# HRT_23D_EBS1_1.net
KiCad netlist of a schematic drawn in Altium Designer
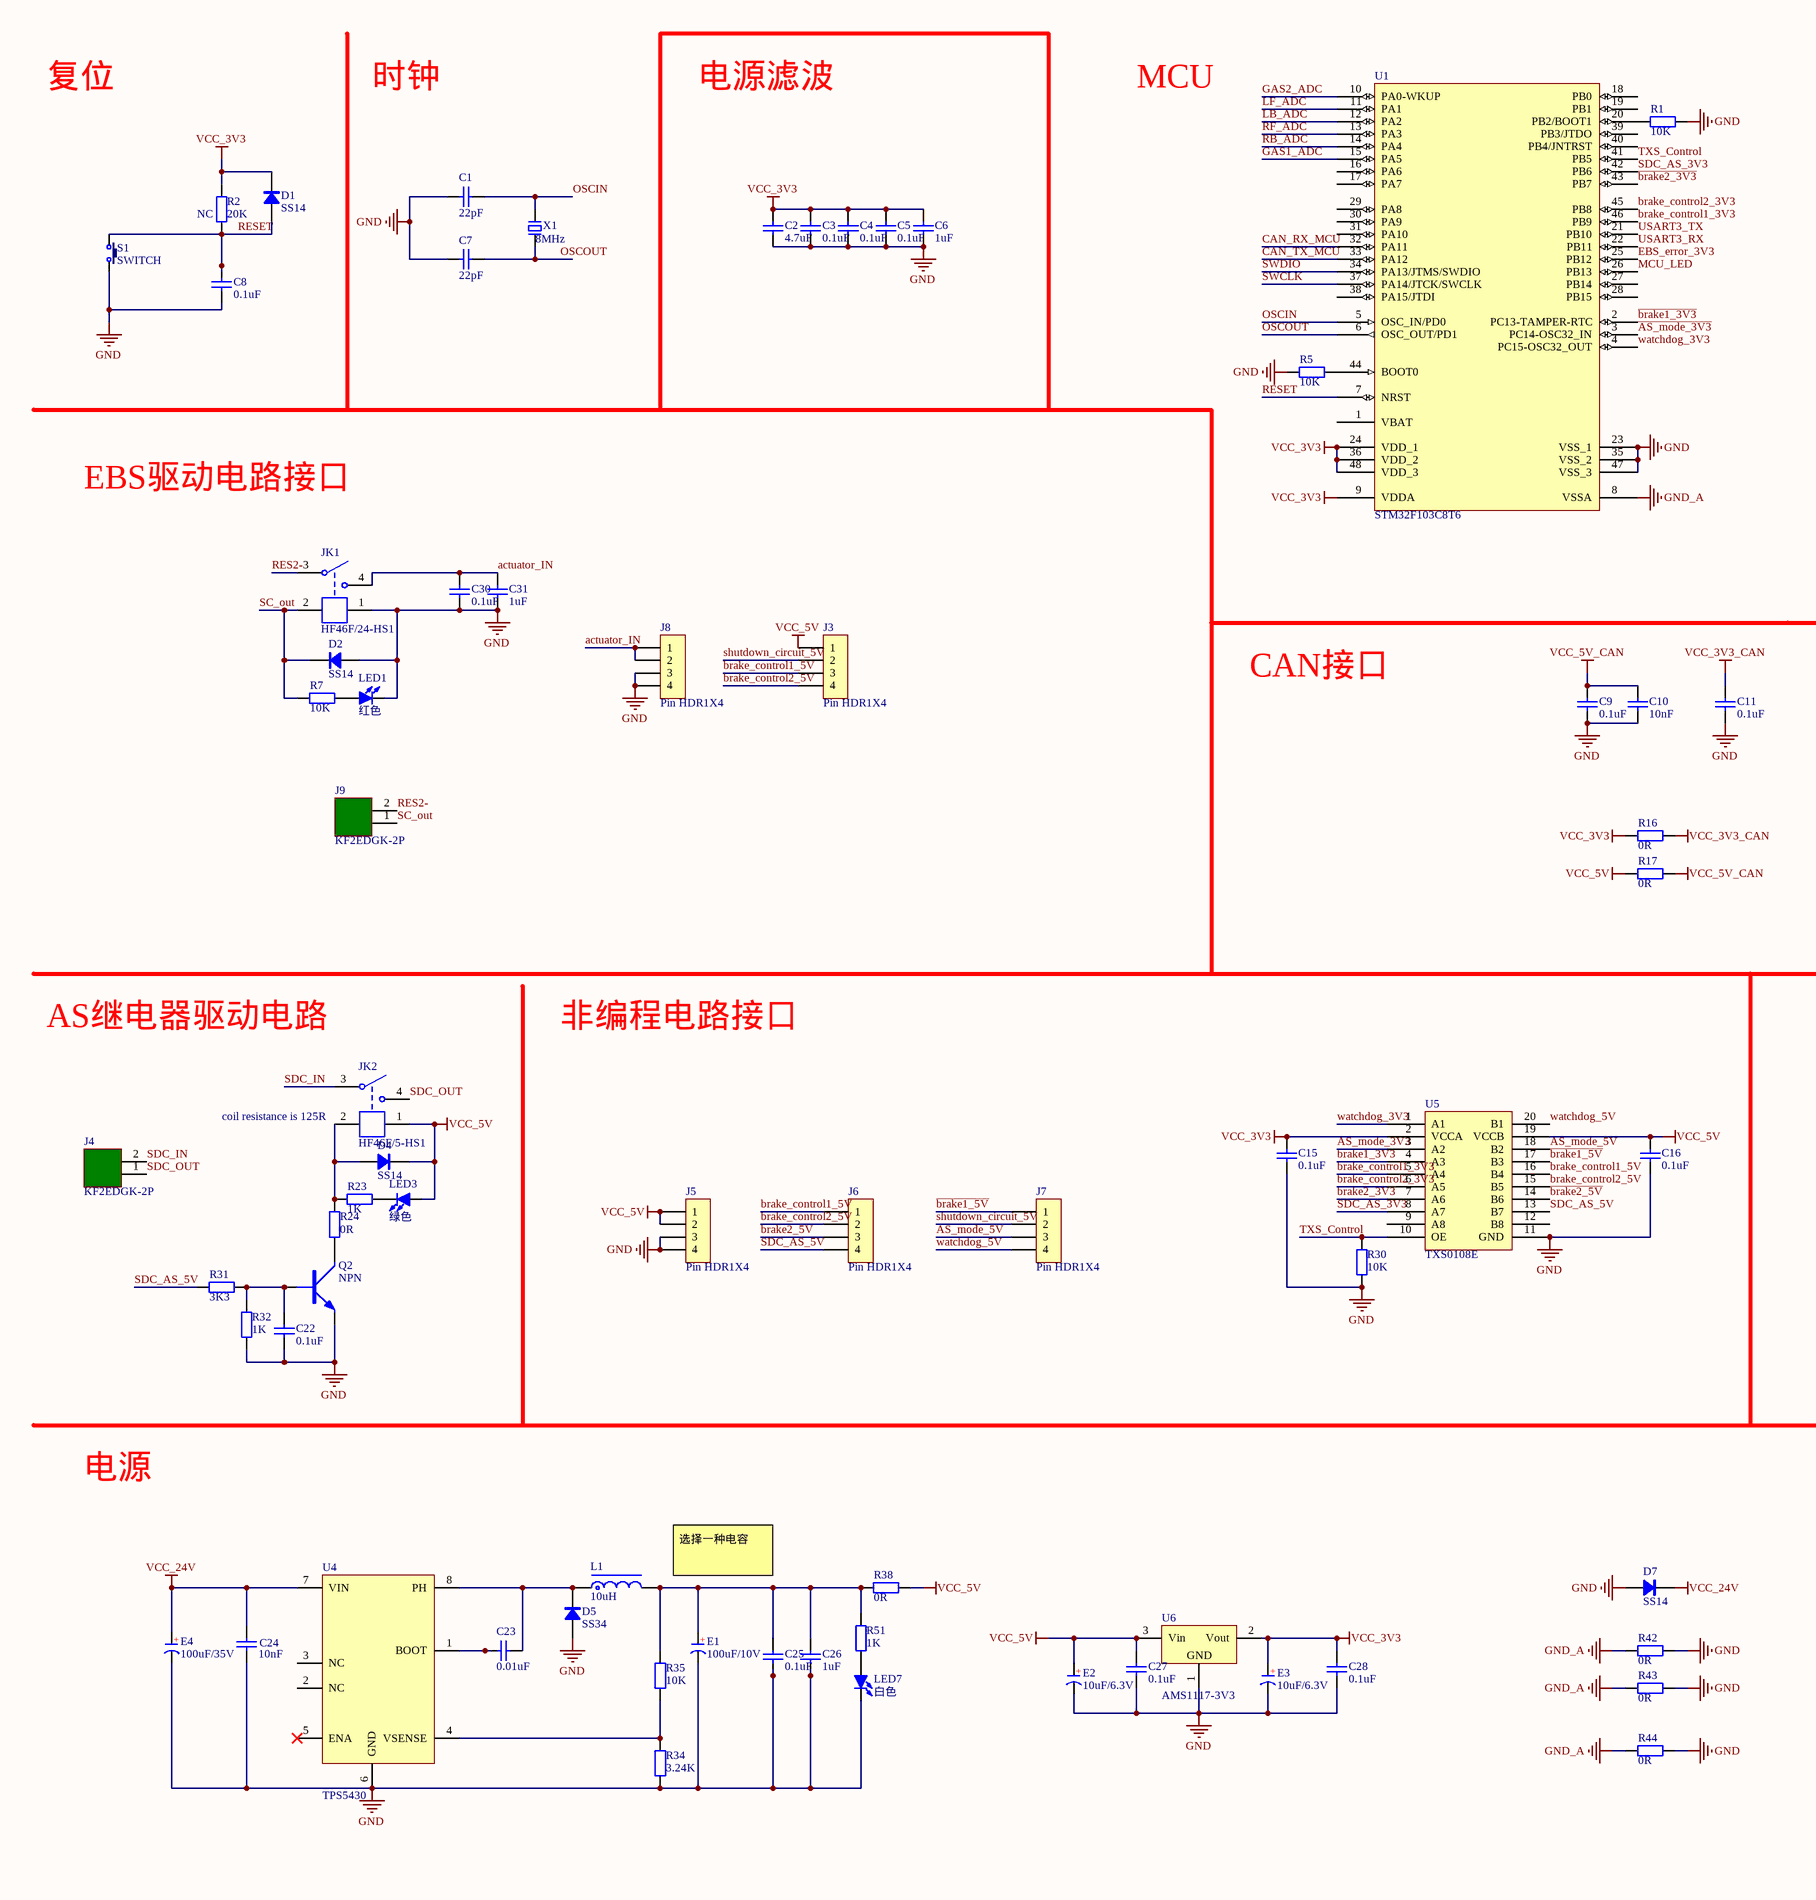
[diagram p0: HRT_23D_EBS1.1.SchDoc, left]
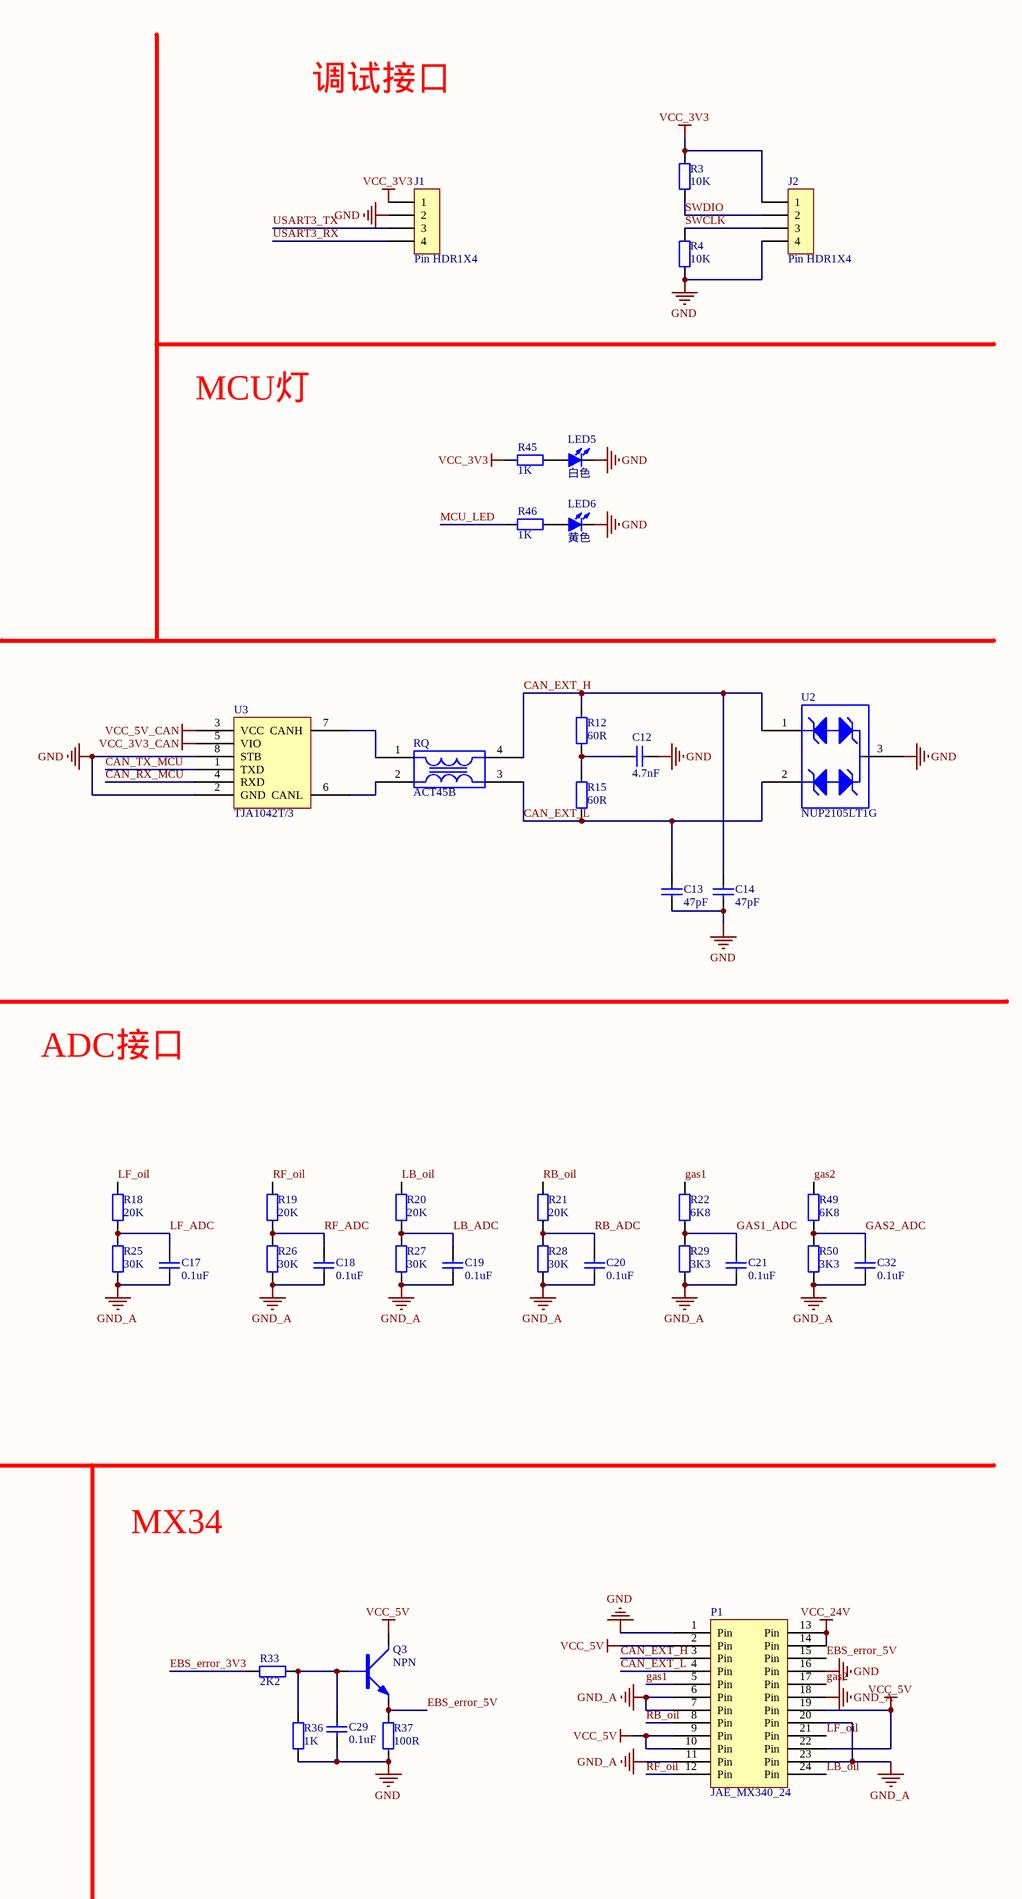
[diagram p1: HRT_23D_EBS1.1.SchDoc, right]

(export (version "E")
  (design (tool "Eeschema 10.0.6"))
  (components
    (comp (ref "C1")
      (value "22pF")
      (footprint "C 0805_M")
      (description "无极性贴片电容")
      (libsource (lib "mainlib") (part "C"))
    )
    (comp (ref "C2")
      (value "4.7uF")
      (footprint "C 0805_M")
      (description "无极性贴片电容")
      (libsource (lib "mainlib") (part "C"))
    )
    (comp (ref "C3")
      (value "0.1uF")
      (footprint "C 0805_M")
      (description "无极性贴片电容")
      (libsource (lib "mainlib") (part "C"))
    )
    (comp (ref "C4")
      (value "0.1uF")
      (footprint "C 0805_M")
      (description "无极性贴片电容")
      (libsource (lib "mainlib") (part "C"))
    )
    (comp (ref "C5")
      (value "0.1uF")
      (footprint "C 0805_M")
      (description "无极性贴片电容")
      (libsource (lib "mainlib") (part "C"))
    )
    (comp (ref "C6")
      (value "1uF")
      (footprint "C 0805_M")
      (description "无极性贴片电容")
      (libsource (lib "mainlib") (part "C"))
    )
    (comp (ref "C7")
      (value "22pF")
      (footprint "C 0805_M")
      (description "无极性贴片电容")
      (libsource (lib "mainlib") (part "C"))
    )
    (comp (ref "C8")
      (value "0.1uF")
      (footprint "C 0805_M")
      (description "无极性贴片电容")
      (libsource (lib "mainlib") (part "C"))
    )
    (comp (ref "C9")
      (value "0.1uF")
      (footprint "C 0805_M")
      (description "无极性贴片电容")
      (libsource (lib "mainlib") (part "C"))
    )
    (comp (ref "C10")
      (value "10nF")
      (footprint "C 0805_M")
      (description "无极性贴片电容")
      (libsource (lib "mainlib") (part "C"))
    )
    (comp (ref "C11")
      (value "0.1uF")
      (footprint "C 0805_M")
      (description "无极性贴片电容")
      (libsource (lib "mainlib") (part "C"))
    )
    (comp (ref "C12")
      (value "4.7nF")
      (footprint "C 0805_M")
      (description "无极性贴片电容")
      (libsource (lib "mainlib") (part "C"))
    )
    (comp (ref "C13")
      (value "47pF")
      (footprint "C 0805_M")
      (description "无极性贴片电容")
      (libsource (lib "mainlib") (part "C"))
    )
    (comp (ref "C14")
      (value "47pF")
      (footprint "C 0805_M")
      (description "无极性贴片电容")
      (libsource (lib "mainlib") (part "C"))
    )
    (comp (ref "C15")
      (value "0.1uF")
      (footprint "C 0805_M")
      (description "无极性贴片电容")
      (libsource (lib "mainlib") (part "C"))
    )
    (comp (ref "C16")
      (value "0.1uF")
      (footprint "C 0805_M")
      (description "无极性贴片电容")
      (libsource (lib "mainlib") (part "C"))
    )
    (comp (ref "C17")
      (value "0.1uF")
      (footprint "C 0805_M")
      (description "无极性贴片电容")
      (libsource (lib "mainlib") (part "C"))
    )
    (comp (ref "C18")
      (value "0.1uF")
      (footprint "C 0805_M")
      (description "无极性贴片电容")
      (libsource (lib "mainlib") (part "C"))
    )
    (comp (ref "C19")
      (value "0.1uF")
      (footprint "C 0805_M")
      (description "无极性贴片电容")
      (libsource (lib "mainlib") (part "C"))
    )
    (comp (ref "C20")
      (value "0.1uF")
      (footprint "C 0805_M")
      (description "无极性贴片电容")
      (libsource (lib "mainlib") (part "C"))
    )
    (comp (ref "C21")
      (value "0.1uF")
      (footprint "C 0805_M")
      (description "无极性贴片电容")
      (libsource (lib "mainlib") (part "C"))
    )
    (comp (ref "C22")
      (value "0.1uF")
      (footprint "C 0805_M")
      (description "无极性贴片电容")
      (libsource (lib "mainlib") (part "C"))
    )
    (comp (ref "C23")
      (value "0.01uF")
      (footprint "C 0805_M")
      (description "无极性贴片电容")
      (libsource (lib "mainlib") (part "C"))
    )
    (comp (ref "C24")
      (value "10nF")
      (footprint "C 0805_M")
      (description "无极性贴片电容")
      (libsource (lib "mainlib") (part "C"))
    )
    (comp (ref "C25")
      (value "0.1uF")
      (footprint "C 0805_M")
      (description "无极性贴片电容")
      (libsource (lib "mainlib") (part "C"))
    )
    (comp (ref "C26")
      (value "1uF")
      (footprint "C 0805_M")
      (description "无极性贴片电容")
      (libsource (lib "mainlib") (part "C"))
    )
    (comp (ref "C27")
      (value "0.1uF")
      (footprint "C 0805_M")
      (description "无极性贴片电容")
      (libsource (lib "mainlib") (part "C"))
    )
    (comp (ref "C28")
      (value "0.1uF")
      (footprint "C 0805_M")
      (description "无极性贴片电容")
      (libsource (lib "mainlib") (part "C"))
    )
    (comp (ref "C29")
      (value "0.1uF")
      (footprint "C 0805_M")
      (description "无极性贴片电容")
      (libsource (lib "mainlib") (part "C"))
    )
    (comp (ref "C30")
      (value "0.1uF")
      (footprint "C 0805_M")
      (description "无极性贴片电容")
      (libsource (lib "mainlib") (part "C"))
    )
    (comp (ref "C31")
      (value "1uF")
      (footprint "C 0805_M")
      (description "无极性贴片电容")
      (libsource (lib "mainlib") (part "C"))
    )
    (comp (ref "C32")
      (value "0.1uF")
      (footprint "C 0805_M")
      (description "无极性贴片电容")
      (libsource (lib "mainlib") (part "C"))
    )
    (comp (ref "D1")
      (value "SS14")
      (footprint "SMA")
      (description "肖特基二极管")
      (fields (field (name "版权归属") "源创客"))
      (libsource (lib "mainlib") (part "SS14"))
    )
    (comp (ref "D2")
      (value "SS14")
      (footprint "SMA")
      (description "肖特基二极管")
      (fields (field (name "版权归属") "源创客"))
      (libsource (lib "mainlib") (part "SS14"))
    )
    (comp (ref "D4")
      (value "SS14")
      (footprint "SMA")
      (description "肖特基二极管")
      (fields (field (name "版权归属") "源创客"))
      (libsource (lib "mainlib") (part "SS14"))
    )
    (comp (ref "D5")
      (value "SS34")
      (footprint "SMA")
      (description "肖特基二极管")
      (fields (field (name "版权归属") "源创客"))
      (libsource (lib "mainlib") (part "SS34"))
    )
    (comp (ref "D7")
      (value "SS14")
      (footprint "SMA")
      (description "肖特基二极管")
      (fields (field (name "版权归属") "源创客"))
      (libsource (lib "mainlib") (part "SS14"))
    )
    (comp (ref "E1")
      (value "100uF/10V")
      (footprint "CM C(5*5.4)")
      (description "贴片电解电容\r\nESR < 0.04R")
      (fields (field (name "版权归属") "源创客"))
      (libsource (lib "mainlib") (part "C-CM"))
    )
    (comp (ref "E2")
      (value "10uF/6.3V")
      (footprint "CD A(3216)")
      (description "贴片钽电容")
      (fields (field (name "版权归属") "源创客"))
      (libsource (lib "mainlib") (part "C-CD"))
    )
    (comp (ref "E3")
      (value "10uF/6.3V")
      (footprint "CD A(3216)")
      (description "贴片钽电容")
      (fields (field (name "版权归属") "源创客"))
      (libsource (lib "mainlib") (part "C-CD"))
    )
    (comp (ref "E4")
      (value "100uF/35V")
      (footprint "CM D(6.3*7.7)")
      (description "贴片电解电容\r\nESR < 0.04R")
      (fields (field (name "版权归属") "源创客"))
      (libsource (lib "mainlib") (part "C-CM"))
    )
    (comp (ref "J1")
      (value "Pin HDR1X4")
      (footprint "Pin HDR1X4/2.54mm-S")
      (libsource (lib "mainlib") (part "Pin HDR1X4"))
    )
    (comp (ref "J2")
      (value "Pin HDR1X4")
      (footprint "Pin HDR1X4/2.54mm-S")
      (libsource (lib "mainlib") (part "Pin HDR1X4"))
    )
    (comp (ref "J3")
      (value "Pin HDR1X4")
      (footprint "Fe-HDR1X4/2.54-S")
      (libsource (lib "mainlib") (part "Pin HDR1X4"))
    )
    (comp (ref "J4")
      (value "KF2EDGK-2P")
      (footprint "KF2EDGK5.08W-2P")
      (libsource (lib "mainlib") (part "KF2EDGK-2P"))
    )
    (comp (ref "J5")
      (value "Pin HDR1X4")
      (footprint "Fe-HDR1X4/2.54-S")
      (libsource (lib "mainlib") (part "Pin HDR1X4"))
    )
    (comp (ref "J6")
      (value "Pin HDR1X4")
      (footprint "Fe-HDR1X4/2.54-S")
      (libsource (lib "mainlib") (part "Pin HDR1X4"))
    )
    (comp (ref "J7")
      (value "Pin HDR1X4")
      (footprint "Fe-HDR1X4/2.54-S")
      (libsource (lib "mainlib") (part "Pin HDR1X4"))
    )
    (comp (ref "J8")
      (value "Pin HDR1X4")
      (footprint "Fe-HDR1X4/2.54-S")
      (libsource (lib "mainlib") (part "Pin HDR1X4"))
    )
    (comp (ref "J9")
      (value "KF2EDGK-2P")
      (footprint "KF2EDGK5.08W-2P")
      (libsource (lib "mainlib") (part "KF2EDGK-2P"))
    )
    (comp (ref "JK1")
      (value "HF46F/24-HS1")
      (footprint "HF46-xx-HS1")
      (description "24V一组常开继电器")
      (fields (field (name "版权归属") "源创客"))
      (libsource (lib "mainlib") (part "HF46F/24-HS1"))
    )
    (comp (ref "JK2")
      (value "HF46F/5-HS1")
      (footprint "HF46-xx-HS1")
      (description "5V一组常开")
      (fields (field (name "版权归属") "源创客"))
      (libsource (lib "mainlib") (part "HF46F/5-HS1"))
    )
    (comp (ref "L1")
      (value "10uH")
      (footprint "SMD 12*12*8mm")
      (description "贴片功率电感")
      (fields (field (name "版权归属") "源创客"))
      (libsource (lib "mainlib") (part "L-CD"))
    )
    (comp (ref "LED1")
      (value "红色")
      (footprint "LED 0805R")
      (description "贴片LED")
      (fields (field (name "版权归属") "源创客"))
      (libsource (lib "mainlib") (part "LED-SMD"))
    )
    (comp (ref "LED3")
      (value "绿色")
      (footprint "LED 0805G")
      (description "贴片LED")
      (fields (field (name "版权归属") "源创客"))
      (libsource (lib "mainlib") (part "LED-SMD"))
    )
    (comp (ref "LED5")
      (value "白色")
      (footprint "LED 0805W")
      (description "贴片LED")
      (fields (field (name "版权归属") "源创客"))
      (libsource (lib "mainlib") (part "LED-SMD"))
    )
    (comp (ref "LED6")
      (value "黄色")
      (footprint "LED 0805Y")
      (description "贴片LED")
      (fields (field (name "版权归属") "源创客"))
      (libsource (lib "mainlib") (part "LED-SMD"))
    )
    (comp (ref "LED7")
      (value "白色")
      (footprint "LED 0805W")
      (description "贴片LED")
      (fields (field (name "版权归属") "源创客"))
      (libsource (lib "mainlib") (part "LED-SMD"))
    )
    (comp (ref "P1")
      (value "JAE_MX340_24")
      (footprint "JAE_MX34_2.2_24 - duplicate")
      (libsource (lib "mainlib") (part "JAE_MX34024NF1"))
    )
    (comp (ref "Q2")
      (value "NPN")
      (footprint "SOT-23")
      (description "NPN三极管")
      (libsource (lib "mainlib") (part "NPN"))
    )
    (comp (ref "Q3")
      (value "NPN")
      (footprint "SOT-23")
      (description "NPN三极管")
      (libsource (lib "mainlib") (part "NPN"))
    )
    (comp (ref "R1")
      (value "10K")
      (footprint "0805R")
      (description "贴片电阻")
      (libsource (lib "") (part "RES_1"))
    )
    (comp (ref "R2")
      (value "20K")
      (footprint "0805R")
      (description "贴片电阻")
      (libsource (lib "mainlib") (part "RES"))
    )
    (comp (ref "R3")
      (value "10K")
      (footprint "0805R")
      (description "贴片电阻")
      (libsource (lib "mainlib") (part "RES"))
    )
    (comp (ref "R4")
      (value "10K")
      (footprint "0805R")
      (description "贴片电阻")
      (libsource (lib "mainlib") (part "RES"))
    )
    (comp (ref "R5")
      (value "10K")
      (footprint "0805R")
      (description "贴片电阻")
      (libsource (lib "") (part "RES_2"))
    )
    (comp (ref "R7")
      (value "10K")
      (footprint "0805R")
      (description "贴片电阻")
      (libsource (lib "") (part "RES_1"))
    )
    (comp (ref "R12")
      (value "60R")
      (footprint "0805R")
      (description "贴片电阻")
      (libsource (lib "mainlib") (part "RES"))
    )
    (comp (ref "R15")
      (value "60R")
      (footprint "0805R")
      (description "贴片电阻")
      (libsource (lib "mainlib") (part "RES"))
    )
    (comp (ref "R16")
      (value "0R")
      (footprint "0805R")
      (description "贴片电阻")
      (libsource (lib "") (part "RES_2"))
    )
    (comp (ref "R17")
      (value "0R")
      (footprint "0805R")
      (description "贴片电阻")
      (libsource (lib "") (part "RES_2"))
    )
    (comp (ref "R18")
      (value "20K")
      (footprint "0805R")
      (description "贴片电阻")
      (libsource (lib "mainlib") (part "RES"))
    )
    (comp (ref "R19")
      (value "20K")
      (footprint "0805R")
      (description "贴片电阻")
      (libsource (lib "mainlib") (part "RES"))
    )
    (comp (ref "R20")
      (value "20K")
      (footprint "0805R")
      (description "贴片电阻")
      (libsource (lib "mainlib") (part "RES"))
    )
    (comp (ref "R21")
      (value "20K")
      (footprint "0805R")
      (description "贴片电阻")
      (libsource (lib "mainlib") (part "RES"))
    )
    (comp (ref "R22")
      (value "6K8")
      (footprint "0805R")
      (description "贴片电阻")
      (libsource (lib "mainlib") (part "RES"))
    )
    (comp (ref "R23")
      (value "1K")
      (footprint "0805R")
      (description "贴片电阻")
      (libsource (lib "") (part "RES_1"))
    )
    (comp (ref "R24")
      (value "0R")
      (footprint "0805R")
      (description "贴片电阻")
      (libsource (lib "") (part "RES_3"))
    )
    (comp (ref "R25")
      (value "30K")
      (footprint "0805R")
      (description "贴片电阻")
      (libsource (lib "mainlib") (part "RES"))
    )
    (comp (ref "R26")
      (value "30K")
      (footprint "0805R")
      (description "贴片电阻")
      (libsource (lib "mainlib") (part "RES"))
    )
    (comp (ref "R27")
      (value "30K")
      (footprint "0805R")
      (description "贴片电阻")
      (libsource (lib "mainlib") (part "RES"))
    )
    (comp (ref "R28")
      (value "30K")
      (footprint "0805R")
      (description "贴片电阻")
      (libsource (lib "mainlib") (part "RES"))
    )
    (comp (ref "R29")
      (value "3K3")
      (footprint "0805R")
      (description "贴片电阻")
      (libsource (lib "mainlib") (part "RES"))
    )
    (comp (ref "R30")
      (value "10K")
      (footprint "0805R")
      (description "贴片电阻")
      (libsource (lib "mainlib") (part "RES"))
    )
    (comp (ref "R31")
      (value "3K3")
      (footprint "0805R")
      (description "贴片电阻")
      (libsource (lib "") (part "RES_1"))
    )
    (comp (ref "R32")
      (value "1K")
      (footprint "0805R")
      (description "贴片电阻")
      (libsource (lib "mainlib") (part "RES"))
    )
    (comp (ref "R33")
      (value "2K2")
      (footprint "0805R")
      (description "贴片电阻")
      (libsource (lib "") (part "RES_1"))
    )
    (comp (ref "R34")
      (value "3.24K")
      (footprint "0805R")
      (description "贴片电阻")
      (libsource (lib "mainlib") (part "RES"))
    )
    (comp (ref "R35")
      (value "10K")
      (footprint "0805R")
      (description "贴片电阻")
      (libsource (lib "mainlib") (part "RES"))
    )
    (comp (ref "R36")
      (value "1K")
      (footprint "0805R")
      (description "贴片电阻")
      (libsource (lib "mainlib") (part "RES"))
    )
    (comp (ref "R37")
      (value "100R")
      (footprint "0805R")
      (description "贴片电阻")
      (libsource (lib "mainlib") (part "RES"))
    )
    (comp (ref "R38")
      (value "0R")
      (footprint "1206R")
      (description "贴片电阻")
      (libsource (lib "") (part "RES_1"))
    )
    (comp (ref "R42")
      (value "0R")
      (footprint "0805R")
      (description "贴片电阻")
      (libsource (lib "") (part "RES_1"))
    )
    (comp (ref "R43")
      (value "0R")
      (footprint "0805R")
      (description "贴片电阻")
      (libsource (lib "") (part "RES_1"))
    )
    (comp (ref "R44")
      (value "0R")
      (footprint "0805R")
      (description "贴片电阻")
      (libsource (lib "") (part "RES_1"))
    )
    (comp (ref "R45")
      (value "1K")
      (footprint "0805R")
      (description "贴片电阻")
      (libsource (lib "") (part "RES_1"))
    )
    (comp (ref "R46")
      (value "1K")
      (footprint "0805R")
      (description "贴片电阻")
      (libsource (lib "") (part "RES_1"))
    )
    (comp (ref "R49")
      (value "6K8")
      (footprint "0805R")
      (description "贴片电阻")
      (libsource (lib "mainlib") (part "RES"))
    )
    (comp (ref "R50")
      (value "3K3")
      (footprint "0805R")
      (description "贴片电阻")
      (libsource (lib "mainlib") (part "RES"))
    )
    (comp (ref "R51")
      (value "1K")
      (footprint "0805R")
      (description "贴片电阻")
      (libsource (lib "mainlib") (part "RES"))
    )
    (comp (ref "RQ")
      (value "ACT45B")
      (footprint "4532")
      (description "共模电感")
      (libsource (lib "mainlib") (part "ACT45B"))
    )
    (comp (ref "S1")
      (value "SWITCH")
      (footprint "TSW SMD-3*6*2.5")
      (description "按键")
      (libsource (lib "mainlib") (part "SWITCH"))
    )
    (comp (ref "U1")
      (value "STM32F103C8T6")
      (footprint "LQFP48 7X7")
      (libsource (lib "mainlib") (part "STM32F103C8T6"))
    )
    (comp (ref "U2")
      (value "NUP2105LT1G")
      (footprint "SOT-23-3P")
      (description "静电管")
      (libsource (lib "mainlib") (part "NUP2105LT1G"))
    )
    (comp (ref "U3")
      (value "TJA1042T/3")
      (footprint "SOP8")
      (description "高速CAN收发器")
      (libsource (lib "HRT_19D_EBS1.1") (part "TJA1042T/3"))
    )
    (comp (ref "U4")
      (value "TPS5430")
      (footprint "SOP8-Pad")
      (description "DCDC降压芯片")
      (libsource (lib "mainlib") (part "TPS5430"))
    )
    (comp (ref "U5")
      (value "TXS0108E")
      (footprint "SSOP20")
      (libsource (lib "digital_chips") (part "TXS0108E"))
    )
    (comp (ref "U6")
      (value "AMS1117-3V3")
      (footprint "SOT223_M")
      (description "三端稳压芯片")
      (fields (field (name "版权归属") "源创客"))
      (libsource (lib "mainlib") (part "AMS1117"))
    )
    (comp (ref "X1")
      (value "8MHz")
      (footprint "OSC 5032-2P")
      (description "两脚无源晶振")
      (libsource (lib "mainlib") (part "XTAL-2P"))
    )
  )
  (nets
    (net (code "1") (name "/CAN_EXT_H") (class "Default")
      (node (ref "C14") (pin "1") (pinfunction "1_1") (pintype "passive"))
      (node (ref "P1") (pin "3") (pinfunction "Pin_3") (pintype "passive"))
      (node (ref "R12") (pin "2") (pinfunction "2_2") (pintype "passive"))
      (node (ref "RQ") (pin "4") (pinfunction "4_4") (pintype "passive"))
      (node (ref "U2") (pin "1") (pinfunction "1_1") (pintype "passive"))
    )
    (net (code "2") (name "/CAN_EXT_L") (class "Default")
      (node (ref "C13") (pin "1") (pinfunction "1_1") (pintype "passive"))
      (node (ref "P1") (pin "4") (pinfunction "Pin_4") (pintype "passive"))
      (node (ref "R15") (pin "1") (pinfunction "1_1") (pintype "passive"))
      (node (ref "RQ") (pin "3") (pinfunction "3_3") (pintype "passive"))
      (node (ref "U2") (pin "2") (pinfunction "2_2") (pintype "passive"))
    )
    (net (code "3") (name "/CAN_RX_MCU") (class "Default")
      (node (ref "U1") (pin "32") (pinfunction "PA11_32") (pintype "bidirectional"))
      (node (ref "U3") (pin "4") (pinfunction "RXD_4") (pintype "passive"))
    )
    (net (code "4") (name "/CAN_TX_MCU") (class "Default")
      (node (ref "U1") (pin "33") (pinfunction "PA12_33") (pintype "bidirectional"))
      (node (ref "U3") (pin "1") (pinfunction "TXD_1") (pintype "passive"))
    )
    (net (code "5") (name "/EBS_error_3V3") (class "Default")
      (node (ref "R33") (pin "2") (pinfunction "2_2") (pintype "passive"))
      (node (ref "U1") (pin "25") (pinfunction "PB12_25") (pintype "bidirectional"))
    )
    (net (code "6") (name "/EBS_error_5V") (class "Default")
      (node (ref "P1") (pin "15") (pinfunction "Pin_15") (pintype "passive"))
      (node (ref "Q3") (pin "E") (pinfunction "E_E") (pintype "passive"))
      (node (ref "R37") (pin "2") (pinfunction "2_2") (pintype "passive"))
    )
    (net (code "7") (name "/GAS1_ADC") (class "Default")
      (node (ref "C21") (pin "1") (pinfunction "1_1") (pintype "passive"))
      (node (ref "R22") (pin "1") (pinfunction "1_1") (pintype "passive"))
      (node (ref "R29") (pin "2") (pinfunction "2_2") (pintype "passive"))
      (node (ref "U1") (pin "15") (pinfunction "PA5_15") (pintype "bidirectional"))
    )
    (net (code "8") (name "/GAS2_ADC") (class "Default")
      (node (ref "C32") (pin "1") (pinfunction "1_1") (pintype "passive"))
      (node (ref "R49") (pin "1") (pinfunction "1_1") (pintype "passive"))
      (node (ref "R50") (pin "2") (pinfunction "2_2") (pintype "passive"))
      (node (ref "U1") (pin "10") (pinfunction "PA0-WKUP_10") (pintype "bidirectional"))
    )
    (net (code "9") (name "/LB_ADC") (class "Default")
      (node (ref "C19") (pin "1") (pinfunction "1_1") (pintype "passive"))
      (node (ref "R20") (pin "1") (pinfunction "1_1") (pintype "passive"))
      (node (ref "R27") (pin "2") (pinfunction "2_2") (pintype "passive"))
      (node (ref "U1") (pin "12") (pinfunction "PA2_12") (pintype "bidirectional"))
    )
    (net (code "10") (name "/LB_oil") (class "Default")
      (node (ref "P1") (pin "24") (pinfunction "Pin_24") (pintype "passive"))
      (node (ref "R20") (pin "2") (pinfunction "2_2") (pintype "passive"))
    )
    (net (code "11") (name "/LF_ADC") (class "Default")
      (node (ref "C17") (pin "1") (pinfunction "1_1") (pintype "passive"))
      (node (ref "R18") (pin "1") (pinfunction "1_1") (pintype "passive"))
      (node (ref "R25") (pin "2") (pinfunction "2_2") (pintype "passive"))
      (node (ref "U1") (pin "11") (pinfunction "PA1_11") (pintype "bidirectional"))
    )
    (net (code "12") (name "/LF_oil") (class "Default")
      (node (ref "P1") (pin "21") (pinfunction "Pin_21") (pintype "passive"))
      (node (ref "R18") (pin "2") (pinfunction "2_2") (pintype "passive"))
    )
    (net (code "13") (name "/MCU_LED") (class "Default")
      (node (ref "R46") (pin "2") (pinfunction "2_2") (pintype "passive"))
      (node (ref "U1") (pin "26") (pinfunction "PB13_26") (pintype "bidirectional"))
    )
    (net (code "14") (name "/OSCIN") (class "Default")
      (node (ref "C1") (pin "2") (pinfunction "2_2") (pintype "passive"))
      (node (ref "U1") (pin "5") (pinfunction "OSC_IN/PD0_5") (pintype "input"))
      (node (ref "X1") (pin "1") (pinfunction "1_1") (pintype "passive"))
    )
    (net (code "15") (name "/OSCOUT") (class "Default")
      (node (ref "C7") (pin "2") (pinfunction "2_2") (pintype "passive"))
      (node (ref "U1") (pin "6") (pinfunction "OSC_OUT/PD1_6") (pintype "output"))
      (node (ref "X1") (pin "2") (pinfunction "2_2") (pintype "passive"))
    )
    (net (code "16") (name "/RB_ADC") (class "Default")
      (node (ref "C20") (pin "1") (pinfunction "1_1") (pintype "passive"))
      (node (ref "R21") (pin "1") (pinfunction "1_1") (pintype "passive"))
      (node (ref "R28") (pin "2") (pinfunction "2_2") (pintype "passive"))
      (node (ref "U1") (pin "14") (pinfunction "PA4_14") (pintype "bidirectional"))
    )
    (net (code "17") (name "/RB_oil") (class "Default")
      (node (ref "P1") (pin "8") (pinfunction "Pin_8") (pintype "passive"))
      (node (ref "R21") (pin "2") (pinfunction "2_2") (pintype "passive"))
    )
    (net (code "18") (name "/RES2-") (class "Default")
      (node (ref "J9") (pin "2") (pinfunction "2_2") (pintype "passive"))
      (node (ref "JK1") (pin "3") (pinfunction "3_3") (pintype "passive"))
    )
    (net (code "19") (name "/RESET") (class "Default")
      (node (ref "C8") (pin "2") (pinfunction "2_2") (pintype "passive"))
      (node (ref "D1") (pin "1") (pinfunction "A_1") (pintype "passive"))
      (node (ref "R2") (pin "1") (pinfunction "1_1") (pintype "passive"))
      (node (ref "S1") (pin "1") (pinfunction "1_1") (pintype "passive"))
      (node (ref "U1") (pin "7") (pinfunction "NRST_7") (pintype "bidirectional"))
    )
    (net (code "20") (name "/RF_ADC") (class "Default")
      (node (ref "C18") (pin "1") (pinfunction "1_1") (pintype "passive"))
      (node (ref "R19") (pin "1") (pinfunction "1_1") (pintype "passive"))
      (node (ref "R26") (pin "2") (pinfunction "2_2") (pintype "passive"))
      (node (ref "U1") (pin "13") (pinfunction "PA3_13") (pintype "bidirectional"))
    )
    (net (code "21") (name "/RF_oil") (class "Default")
      (node (ref "P1") (pin "12") (pinfunction "Pin_12") (pintype "passive"))
      (node (ref "R19") (pin "2") (pinfunction "2_2") (pintype "passive"))
    )
    (net (code "22") (name "/SC_out") (class "Default")
      (node (ref "D2") (pin "2") (pinfunction "K_2") (pintype "passive"))
      (node (ref "J9") (pin "1") (pinfunction "1_1") (pintype "passive"))
      (node (ref "JK1") (pin "2") (pinfunction "2_2") (pintype "passive"))
      (node (ref "R7") (pin "2") (pinfunction "2_2") (pintype "passive"))
    )
    (net (code "23") (name "/SDC_AS_3V3") (class "Default")
      (node (ref "U1") (pin "42") (pinfunction "PB6_42") (pintype "bidirectional"))
      (node (ref "U5") (pin "8") (pinfunction "A7_8") (pintype "passive"))
    )
    (net (code "24") (name "/SDC_AS_5V") (class "Default")
      (node (ref "J6") (pin "4") (pinfunction "4_4") (pintype "passive"))
      (node (ref "R31") (pin "2") (pinfunction "2_2") (pintype "passive"))
      (node (ref "U5") (pin "13") (pinfunction "B7_13") (pintype "passive"))
    )
    (net (code "25") (name "/SDC_IN") (class "Default")
      (node (ref "J4") (pin "2") (pinfunction "2_2") (pintype "passive"))
      (node (ref "JK2") (pin "3") (pinfunction "3_3") (pintype "passive"))
    )
    (net (code "26") (name "/SDC_OUT") (class "Default")
      (node (ref "J4") (pin "1") (pinfunction "1_1") (pintype "passive"))
      (node (ref "JK2") (pin "4") (pinfunction "4_4") (pintype "passive"))
    )
    (net (code "27") (name "/SWCLK") (class "Default")
      (node (ref "J2") (pin "3") (pinfunction "3_3") (pintype "passive"))
      (node (ref "R4") (pin "2") (pinfunction "2_2") (pintype "passive"))
      (node (ref "U1") (pin "37") (pinfunction "PA14/JTCK/SWCLK_37") (pintype "bidirectional"))
    )
    (net (code "28") (name "/SWDIO") (class "Default")
      (node (ref "J2") (pin "2") (pinfunction "2_2") (pintype "passive"))
      (node (ref "R3") (pin "1") (pinfunction "1_1") (pintype "passive"))
      (node (ref "U1") (pin "34") (pinfunction "PA13/JTMS/SWDIO_34") (pintype "bidirectional"))
    )
    (net (code "29") (name "/TXS_Control") (class "Default")
      (node (ref "R30") (pin "2") (pinfunction "2_2") (pintype "passive"))
      (node (ref "U1") (pin "41") (pinfunction "PB5_41") (pintype "bidirectional"))
      (node (ref "U5") (pin "10") (pinfunction "OE_10") (pintype "passive"))
    )
    (net (code "30") (name "/USART3_RX") (class "Default")
      (node (ref "J1") (pin "4") (pinfunction "4_4") (pintype "passive"))
      (node (ref "U1") (pin "22") (pinfunction "PB11_22") (pintype "bidirectional"))
    )
    (net (code "31") (name "/USART3_TX") (class "Default")
      (node (ref "J1") (pin "3") (pinfunction "3_3") (pintype "passive"))
      (node (ref "U1") (pin "21") (pinfunction "PB10_21") (pintype "bidirectional"))
    )
    (net (code "32") (name "/actuator_IN") (class "Default")
      (node (ref "C30") (pin "1") (pinfunction "1_1") (pintype "passive"))
      (node (ref "C31") (pin "1") (pinfunction "1_1") (pintype "passive"))
      (node (ref "J8") (pin "1") (pinfunction "1_1") (pintype "passive"))
      (node (ref "J8") (pin "2") (pinfunction "2_2") (pintype "passive"))
      (node (ref "JK1") (pin "4") (pinfunction "4_4") (pintype "passive"))
    )
    (net (code "33") (name "/brake_control1_3V3") (class "Default")
      (node (ref "U1") (pin "46") (pinfunction "PB9_46") (pintype "bidirectional"))
      (node (ref "U5") (pin "5") (pinfunction "A4_5") (pintype "passive"))
    )
    (net (code "34") (name "/brake_control1_5V") (class "Default")
      (node (ref "J3") (pin "3") (pinfunction "3_3") (pintype "passive"))
      (node (ref "J6") (pin "1") (pinfunction "1_1") (pintype "passive"))
      (node (ref "U5") (pin "16") (pinfunction "B4_16") (pintype "passive"))
    )
    (net (code "35") (name "/brake_control2_3V3") (class "Default")
      (node (ref "U1") (pin "45") (pinfunction "PB8_45") (pintype "bidirectional"))
      (node (ref "U5") (pin "6") (pinfunction "A5_6") (pintype "passive"))
    )
    (net (code "36") (name "/brake_control2_5V") (class "Default")
      (node (ref "J3") (pin "4") (pinfunction "4_4") (pintype "passive"))
      (node (ref "J6") (pin "2") (pinfunction "2_2") (pintype "passive"))
      (node (ref "U5") (pin "15") (pinfunction "B5_15") (pintype "passive"))
    )
    (net (code "37") (name "/gas1") (class "Default")
      (node (ref "P1") (pin "5") (pinfunction "Pin_5") (pintype "passive"))
      (node (ref "R22") (pin "2") (pinfunction "2_2") (pintype "passive"))
    )
    (net (code "38") (name "/gas2") (class "Default")
      (node (ref "P1") (pin "17") (pinfunction "Pin_17") (pintype "passive"))
      (node (ref "R49") (pin "2") (pinfunction "2_2") (pintype "passive"))
    )
    (net (code "39") (name "/shutdown_circuit_5V") (class "Default")
      (node (ref "J3") (pin "2") (pinfunction "2_2") (pintype "passive"))
      (node (ref "J7") (pin "2") (pinfunction "2_2") (pintype "passive"))
    )
    (net (code "40") (name "/watchdog_3V3") (class "Default")
      (node (ref "U1") (pin "4") (pinfunction "PC15-OSC32_OUT_4") (pintype "bidirectional"))
      (node (ref "U5") (pin "1") (pinfunction "A1_1") (pintype "passive"))
    )
    (net (code "41") (name "/watchdog_5V") (class "Default")
      (node (ref "J7") (pin "4") (pinfunction "4_4") (pintype "passive"))
      (node (ref "U5") (pin "20") (pinfunction "B1_20") (pintype "passive"))
    )
    (net (code "42") (name "/~{AS_mode_3V3}") (class "Default")
      (node (ref "U1") (pin "3") (pinfunction "PC14-OSC32_IN_3") (pintype "bidirectional"))
      (node (ref "U5") (pin "3") (pinfunction "A2_3") (pintype "passive"))
    )
    (net (code "43") (name "/~{AS_mode_5V}") (class "Default")
      (node (ref "J7") (pin "3") (pinfunction "3_3") (pintype "passive"))
      (node (ref "U5") (pin "18") (pinfunction "_B2_18") (pintype "passive"))
    )
    (net (code "44") (name "/~{brake1_3V3}") (class "Default")
      (node (ref "U1") (pin "2") (pinfunction "PC13-TAMPER-RTC_2") (pintype "bidirectional"))
      (node (ref "U5") (pin "4") (pinfunction "A3_4") (pintype "passive"))
    )
    (net (code "45") (name "/~{brake1_5V}") (class "Default")
      (node (ref "J7") (pin "1") (pinfunction "1_1") (pintype "passive"))
      (node (ref "U5") (pin "17") (pinfunction "B3_17") (pintype "passive"))
    )
    (net (code "46") (name "/~{brake2_3V3}") (class "Default")
      (node (ref "U1") (pin "43") (pinfunction "PB7_43") (pintype "bidirectional"))
      (node (ref "U5") (pin "7") (pinfunction "A6_7") (pintype "passive"))
    )
    (net (code "47") (name "/~{brake2_5V}") (class "Default")
      (node (ref "J6") (pin "3") (pinfunction "3_3") (pintype "passive"))
      (node (ref "U5") (pin "14") (pinfunction "B6_14") (pintype "passive"))
    )
    (net (code "48") (name "GND") (class "Default")
      (node (ref "C1") (pin "1") (pinfunction "1_1") (pintype "passive"))
      (node (ref "C10") (pin "1") (pinfunction "1_1") (pintype "passive"))
      (node (ref "C11") (pin "1") (pinfunction "1_1") (pintype "passive"))
      (node (ref "C12") (pin "1") (pinfunction "1_1") (pintype "passive"))
      (node (ref "C13") (pin "2") (pinfunction "2_2") (pintype "passive"))
      (node (ref "C14") (pin "2") (pinfunction "2_2") (pintype "passive"))
      (node (ref "C15") (pin "2") (pinfunction "2_2") (pintype "passive"))
      (node (ref "C16") (pin "2") (pinfunction "2_2") (pintype "passive"))
      (node (ref "C2") (pin "1") (pinfunction "1_1") (pintype "passive"))
      (node (ref "C22") (pin "2") (pinfunction "2_2") (pintype "passive"))
      (node (ref "C24") (pin "2") (pinfunction "2_2") (pintype "passive"))
      (node (ref "C25") (pin "2") (pinfunction "2_2") (pintype "passive"))
      (node (ref "C26") (pin "2") (pinfunction "2_2") (pintype "passive"))
      (node (ref "C27") (pin "2") (pinfunction "2_2") (pintype "passive"))
      (node (ref "C28") (pin "2") (pinfunction "2_2") (pintype "passive"))
      (node (ref "C29") (pin "2") (pinfunction "2_2") (pintype "passive"))
      (node (ref "C3") (pin "1") (pinfunction "1_1") (pintype "passive"))
      (node (ref "C30") (pin "2") (pinfunction "2_2") (pintype "passive"))
      (node (ref "C31") (pin "2") (pinfunction "2_2") (pintype "passive"))
      (node (ref "C4") (pin "1") (pinfunction "1_1") (pintype "passive"))
      (node (ref "C5") (pin "1") (pinfunction "1_1") (pintype "passive"))
      (node (ref "C6") (pin "1") (pinfunction "1_1") (pintype "passive"))
      (node (ref "C7") (pin "1") (pinfunction "1_1") (pintype "passive"))
      (node (ref "C8") (pin "1") (pinfunction "1_1") (pintype "passive"))
      (node (ref "C9") (pin "1") (pinfunction "1_1") (pintype "passive"))
      (node (ref "D2") (pin "1") (pinfunction "A_1") (pintype "passive"))
      (node (ref "D5") (pin "1") (pinfunction "A_1") (pintype "passive"))
      (node (ref "D7") (pin "1") (pinfunction "A_1") (pintype "passive"))
      (node (ref "E1") (pin "2") (pinfunction "K_2") (pintype "passive"))
      (node (ref "E2") (pin "1") (pinfunction "K_1") (pintype "passive"))
      (node (ref "E3") (pin "1") (pinfunction "K_1") (pintype "passive"))
      (node (ref "E4") (pin "2") (pinfunction "K_2") (pintype "passive"))
      (node (ref "J1") (pin "2") (pinfunction "2_2") (pintype "passive"))
      (node (ref "J2") (pin "4") (pinfunction "4_4") (pintype "passive"))
      (node (ref "J5") (pin "3") (pinfunction "3_3") (pintype "passive"))
      (node (ref "J5") (pin "4") (pinfunction "4_4") (pintype "passive"))
      (node (ref "J8") (pin "3") (pinfunction "3_3") (pintype "passive"))
      (node (ref "J8") (pin "4") (pinfunction "4_4") (pintype "passive"))
      (node (ref "JK1") (pin "1") (pinfunction "1_1") (pintype "passive"))
      (node (ref "LED1") (pin "2") (pinfunction "K_2") (pintype "passive"))
      (node (ref "LED5") (pin "2") (pinfunction "K_2") (pintype "passive"))
      (node (ref "LED6") (pin "2") (pinfunction "K_2") (pintype "passive"))
      (node (ref "LED7") (pin "2") (pinfunction "K_2") (pintype "passive"))
      (node (ref "P1") (pin "1") (pinfunction "Pin_1") (pintype "passive"))
      (node (ref "P1") (pin "16") (pinfunction "Pin_16") (pintype "passive"))
      (node (ref "Q2") (pin "E") (pinfunction "E_E") (pintype "passive"))
      (node (ref "R1") (pin "1") (pinfunction "1_1") (pintype "passive"))
      (node (ref "R30") (pin "1") (pinfunction "1_1") (pintype "passive"))
      (node (ref "R32") (pin "1") (pinfunction "1_1") (pintype "passive"))
      (node (ref "R34") (pin "1") (pinfunction "1_1") (pintype "passive"))
      (node (ref "R36") (pin "1") (pinfunction "1_1") (pintype "passive"))
      (node (ref "R37") (pin "1") (pinfunction "1_1") (pintype "passive"))
      (node (ref "R4") (pin "1") (pinfunction "1_1") (pintype "passive"))
      (node (ref "R42") (pin "1") (pinfunction "1_1") (pintype "passive"))
      (node (ref "R43") (pin "1") (pinfunction "1_1") (pintype "passive"))
      (node (ref "R44") (pin "1") (pinfunction "1_1") (pintype "passive"))
      (node (ref "R5") (pin "1") (pinfunction "1_1") (pintype "passive"))
      (node (ref "S1") (pin "2") (pinfunction "2_2") (pintype "passive"))
      (node (ref "U1") (pin "23") (pinfunction "VSS_1_23") (pintype "power_in"))
      (node (ref "U1") (pin "35") (pinfunction "VSS_2_35") (pintype "power_in"))
      (node (ref "U1") (pin "47") (pinfunction "VSS_3_47") (pintype "power_in"))
      (node (ref "U2") (pin "3") (pinfunction "3_3") (pintype "passive"))
      (node (ref "U3") (pin "2") (pinfunction "GND_2") (pintype "passive"))
      (node (ref "U3") (pin "8") (pinfunction "STB_8") (pintype "passive"))
      (node (ref "U4") (pin "6") (pinfunction "GND_6") (pintype "passive"))
      (node (ref "U5") (pin "11") (pinfunction "GND_11") (pintype "passive"))
      (node (ref "U6") (pin "1") (pinfunction "GND_1") (pintype "passive"))
    )
    (net (code "49") (name "GND_A") (class "Default")
      (node (ref "C17") (pin "2") (pinfunction "2_2") (pintype "passive"))
      (node (ref "C18") (pin "2") (pinfunction "2_2") (pintype "passive"))
      (node (ref "C19") (pin "2") (pinfunction "2_2") (pintype "passive"))
      (node (ref "C20") (pin "2") (pinfunction "2_2") (pintype "passive"))
      (node (ref "C21") (pin "2") (pinfunction "2_2") (pintype "passive"))
      (node (ref "C32") (pin "2") (pinfunction "2_2") (pintype "passive"))
      (node (ref "P1") (pin "11") (pinfunction "Pin_11") (pintype "passive"))
      (node (ref "P1") (pin "18") (pinfunction "Pin_18") (pintype "passive"))
      (node (ref "P1") (pin "20") (pinfunction "Pin_20") (pintype "passive"))
      (node (ref "P1") (pin "23") (pinfunction "Pin_23") (pintype "passive"))
      (node (ref "P1") (pin "6") (pinfunction "Pin_6") (pintype "passive"))
      (node (ref "P1") (pin "7") (pinfunction "Pin_7") (pintype "passive"))
      (node (ref "R25") (pin "1") (pinfunction "1_1") (pintype "passive"))
      (node (ref "R26") (pin "1") (pinfunction "1_1") (pintype "passive"))
      (node (ref "R27") (pin "1") (pinfunction "1_1") (pintype "passive"))
      (node (ref "R28") (pin "1") (pinfunction "1_1") (pintype "passive"))
      (node (ref "R29") (pin "1") (pinfunction "1_1") (pintype "passive"))
      (node (ref "R42") (pin "2") (pinfunction "2_2") (pintype "passive"))
      (node (ref "R43") (pin "2") (pinfunction "2_2") (pintype "passive"))
      (node (ref "R44") (pin "2") (pinfunction "2_2") (pintype "passive"))
      (node (ref "R50") (pin "1") (pinfunction "1_1") (pintype "passive"))
      (node (ref "U1") (pin "8") (pinfunction "VSSA_8") (pintype "power_in"))
    )
    (net (code "50") (name "Net-(C12-Pad2)") (class "Default")
      (node (ref "C12") (pin "2") (pinfunction "2_2") (pintype "passive"))
      (node (ref "R12") (pin "1") (pinfunction "1_1") (pintype "passive"))
      (node (ref "R15") (pin "2") (pinfunction "2_2") (pintype "passive"))
    )
    (net (code "51") (name "Net-(C22-Pad1)") (class "Default")
      (node (ref "C22") (pin "1") (pinfunction "1_1") (pintype "passive"))
      (node (ref "Q2") (pin "B") (pinfunction "B_B") (pintype "passive"))
      (node (ref "R31") (pin "1") (pinfunction "1_1") (pintype "passive"))
      (node (ref "R32") (pin "2") (pinfunction "2_2") (pintype "passive"))
    )
    (net (code "52") (name "Net-(C29-Pad1)") (class "Default")
      (node (ref "C29") (pin "1") (pinfunction "1_1") (pintype "passive"))
      (node (ref "Q3") (pin "B") (pinfunction "B_B") (pintype "passive"))
      (node (ref "R33") (pin "1") (pinfunction "1_1") (pintype "passive"))
      (node (ref "R36") (pin "2") (pinfunction "2_2") (pintype "passive"))
    )
    (net (code "53") (name "Net-(D4-A)") (class "Default")
      (node (ref "D4") (pin "1") (pinfunction "A_1") (pintype "passive"))
      (node (ref "JK2") (pin "2") (pinfunction "2_2") (pintype "passive"))
      (node (ref "R23") (pin "2") (pinfunction "2_2") (pintype "passive"))
      (node (ref "R24") (pin "1") (pinfunction "1_1") (pintype "passive"))
    )
    (net (code "54") (name "Net-(D5-K)") (class "Default")
      (node (ref "C23") (pin "2") (pinfunction "2_2") (pintype "passive"))
      (node (ref "D5") (pin "2") (pinfunction "K_2") (pintype "passive"))
      (node (ref "L1") (pin "1") (pinfunction "1_1") (pintype "passive"))
      (node (ref "U4") (pin "8") (pinfunction "PH_8") (pintype "passive"))
    )
    (net (code "55") (name "Net-(E1-A)") (class "Default")
      (node (ref "C25") (pin "1") (pinfunction "1_1") (pintype "passive"))
      (node (ref "C26") (pin "1") (pinfunction "1_1") (pintype "passive"))
      (node (ref "E1") (pin "1") (pinfunction "A_1") (pintype "passive"))
      (node (ref "L1") (pin "2") (pinfunction "2_2") (pintype "passive"))
      (node (ref "R35") (pin "2") (pinfunction "2_2") (pintype "passive"))
      (node (ref "R38") (pin "2") (pinfunction "2_2") (pintype "passive"))
      (node (ref "R51") (pin "2") (pinfunction "2_2") (pintype "passive"))
    )
    (net (code "56") (name "Net-(LED1-A)") (class "Default")
      (node (ref "LED1") (pin "1") (pinfunction "A_1") (pintype "passive"))
      (node (ref "R7") (pin "1") (pinfunction "1_1") (pintype "passive"))
    )
    (net (code "57") (name "Net-(LED3-K)") (class "Default")
      (node (ref "LED3") (pin "2") (pinfunction "K_2") (pintype "passive"))
      (node (ref "R23") (pin "1") (pinfunction "1_1") (pintype "passive"))
    )
    (net (code "58") (name "Net-(LED5-A)") (class "Default")
      (node (ref "LED5") (pin "1") (pinfunction "A_1") (pintype "passive"))
      (node (ref "R45") (pin "1") (pinfunction "1_1") (pintype "passive"))
    )
    (net (code "59") (name "Net-(LED6-A)") (class "Default")
      (node (ref "LED6") (pin "1") (pinfunction "A_1") (pintype "passive"))
      (node (ref "R46") (pin "1") (pinfunction "1_1") (pintype "passive"))
    )
    (net (code "60") (name "Net-(LED7-A)") (class "Default")
      (node (ref "LED7") (pin "1") (pinfunction "A_1") (pintype "passive"))
      (node (ref "R51") (pin "1") (pinfunction "1_1") (pintype "passive"))
    )
    (net (code "61") (name "Net-(Q2-PadC)") (class "Default")
      (node (ref "Q2") (pin "C") (pinfunction "C_C") (pintype "passive"))
      (node (ref "R24") (pin "2") (pinfunction "2_2") (pintype "passive"))
    )
    (net (code "62") (name "Net-(U1-BOOT0)") (class "Default")
      (node (ref "R5") (pin "2") (pinfunction "2_2") (pintype "passive"))
      (node (ref "U1") (pin "44") (pinfunction "BOOT0_44") (pintype "input"))
    )
    (net (code "63") (name "Net-(U1-PB2{slash}BOOT1)") (class "Default")
      (node (ref "R1") (pin "2") (pinfunction "2_2") (pintype "passive"))
      (node (ref "U1") (pin "20") (pinfunction "PB2/BOOT1_20") (pintype "bidirectional"))
    )
    (net (code "64") (name "Net-(U3-CANH)") (class "Default")
      (node (ref "RQ") (pin "1") (pinfunction "1_1") (pintype "passive"))
      (node (ref "U3") (pin "7") (pinfunction "CANH_7") (pintype "passive"))
    )
    (net (code "65") (name "Net-(U3-CANL)") (class "Default")
      (node (ref "RQ") (pin "2") (pinfunction "2_2") (pintype "passive"))
      (node (ref "U3") (pin "6") (pinfunction "CANL_6") (pintype "passive"))
    )
    (net (code "66") (name "Net-(U4-BOOT)") (class "Default")
      (node (ref "C23") (pin "1") (pinfunction "1_1") (pintype "passive"))
      (node (ref "U4") (pin "1") (pinfunction "BOOT_1") (pintype "passive"))
    )
    (net (code "67") (name "Net-(U4-VSENSE)") (class "Default")
      (node (ref "R34") (pin "2") (pinfunction "2_2") (pintype "passive"))
      (node (ref "R35") (pin "1") (pinfunction "1_1") (pintype "passive"))
      (node (ref "U4") (pin "4") (pinfunction "VSENSE_4") (pintype "passive"))
    )
    (net (code "68") (name "VCC_3V3") (class "Default")
      (node (ref "C15") (pin "1") (pinfunction "1_1") (pintype "passive"))
      (node (ref "C2") (pin "2") (pinfunction "2_2") (pintype "passive"))
      (node (ref "C28") (pin "1") (pinfunction "1_1") (pintype "passive"))
      (node (ref "C3") (pin "2") (pinfunction "2_2") (pintype "passive"))
      (node (ref "C4") (pin "2") (pinfunction "2_2") (pintype "passive"))
      (node (ref "C5") (pin "2") (pinfunction "2_2") (pintype "passive"))
      (node (ref "C6") (pin "2") (pinfunction "2_2") (pintype "passive"))
      (node (ref "D1") (pin "2") (pinfunction "K_2") (pintype "passive"))
      (node (ref "E3") (pin "2") (pinfunction "A_2") (pintype "passive"))
      (node (ref "J1") (pin "1") (pinfunction "1_1") (pintype "passive"))
      (node (ref "J2") (pin "1") (pinfunction "1_1") (pintype "passive"))
      (node (ref "R16") (pin "1") (pinfunction "1_1") (pintype "passive"))
      (node (ref "R2") (pin "2") (pinfunction "2_2") (pintype "passive"))
      (node (ref "R3") (pin "2") (pinfunction "2_2") (pintype "passive"))
      (node (ref "R45") (pin "2") (pinfunction "2_2") (pintype "passive"))
      (node (ref "U1") (pin "24") (pinfunction "VDD_1_24") (pintype "power_in"))
      (node (ref "U1") (pin "36") (pinfunction "VDD_2_36") (pintype "power_in"))
      (node (ref "U1") (pin "48") (pinfunction "VDD_3_48") (pintype "power_in"))
      (node (ref "U1") (pin "9") (pinfunction "VDDA_9") (pintype "power_in"))
      (node (ref "U5") (pin "2") (pinfunction "VCCA_2") (pintype "passive"))
      (node (ref "U6") (pin "2") (pinfunction "Vout_2") (pintype "passive"))
    )
    (net (code "69") (name "VCC_3V3_CAN") (class "Default")
      (node (ref "C11") (pin "2") (pinfunction "2_2") (pintype "passive"))
      (node (ref "R16") (pin "2") (pinfunction "2_2") (pintype "passive"))
      (node (ref "U3") (pin "5") (pinfunction "VIO_5") (pintype "passive"))
    )
    (net (code "70") (name "VCC_5V") (class "Default")
      (node (ref "C16") (pin "1") (pinfunction "1_1") (pintype "passive"))
      (node (ref "C27") (pin "1") (pinfunction "1_1") (pintype "passive"))
      (node (ref "D4") (pin "2") (pinfunction "K_2") (pintype "passive"))
      (node (ref "E2") (pin "2") (pinfunction "A_2") (pintype "passive"))
      (node (ref "J3") (pin "1") (pinfunction "1_1") (pintype "passive"))
      (node (ref "J5") (pin "1") (pinfunction "1_1") (pintype "passive"))
      (node (ref "J5") (pin "2") (pinfunction "2_2") (pintype "passive"))
      (node (ref "JK2") (pin "1") (pinfunction "1_1") (pintype "passive"))
      (node (ref "LED3") (pin "1") (pinfunction "A_1") (pintype "passive"))
      (node (ref "P1") (pin "10") (pinfunction "Pin_10") (pintype "passive"))
      (node (ref "P1") (pin "19") (pinfunction "Pin_19") (pintype "passive"))
      (node (ref "P1") (pin "2") (pinfunction "Pin_2") (pintype "passive"))
      (node (ref "P1") (pin "22") (pinfunction "Pin_22") (pintype "passive"))
      (node (ref "P1") (pin "9") (pinfunction "Pin_9") (pintype "passive"))
      (node (ref "Q3") (pin "C") (pinfunction "C_C") (pintype "passive"))
      (node (ref "R17") (pin "1") (pinfunction "1_1") (pintype "passive"))
      (node (ref "R38") (pin "1") (pinfunction "1_1") (pintype "passive"))
      (node (ref "U5") (pin "19") (pinfunction "VCCB_19") (pintype "passive"))
      (node (ref "U6") (pin "3") (pinfunction "Vin_3") (pintype "passive"))
    )
    (net (code "71") (name "VCC_5V_CAN") (class "Default")
      (node (ref "C10") (pin "2") (pinfunction "2_2") (pintype "passive"))
      (node (ref "C9") (pin "2") (pinfunction "2_2") (pintype "passive"))
      (node (ref "R17") (pin "2") (pinfunction "2_2") (pintype "passive"))
      (node (ref "U3") (pin "3") (pinfunction "VCC_3") (pintype "passive"))
    )
    (net (code "72") (name "VCC_24V") (class "Default")
      (node (ref "C24") (pin "1") (pinfunction "1_1") (pintype "passive"))
      (node (ref "D7") (pin "2") (pinfunction "K_2") (pintype "passive"))
      (node (ref "E4") (pin "1") (pinfunction "A_1") (pintype "passive"))
      (node (ref "P1") (pin "13") (pinfunction "Pin_13") (pintype "passive"))
      (node (ref "P1") (pin "14") (pinfunction "Pin_14") (pintype "passive"))
      (node (ref "U4") (pin "7") (pinfunction "VIN_7") (pintype "passive"))
    )
    (net (code "73") (name "unconnected-(U1-PA6-Pad16)") (class "Default")
      (node (ref "U1") (pin "16") (pinfunction "PA6_16") (pintype "bidirectional"))
    )
    (net (code "74") (name "unconnected-(U1-PA7-Pad17)") (class "Default")
      (node (ref "U1") (pin "17") (pinfunction "PA7_17") (pintype "bidirectional"))
    )
    (net (code "75") (name "unconnected-(U1-PA8-Pad29)") (class "Default")
      (node (ref "U1") (pin "29") (pinfunction "PA8_29") (pintype "bidirectional"))
    )
    (net (code "76") (name "unconnected-(U1-PA9-Pad30)") (class "Default")
      (node (ref "U1") (pin "30") (pinfunction "PA9_30") (pintype "bidirectional"))
    )
    (net (code "77") (name "unconnected-(U1-PA10-Pad31)") (class "Default")
      (node (ref "U1") (pin "31") (pinfunction "PA10_31") (pintype "bidirectional"))
    )
    (net (code "78") (name "unconnected-(U1-PA15{slash}JTDI-Pad38)") (class "Default")
      (node (ref "U1") (pin "38") (pinfunction "PA15/JTDI_38") (pintype "bidirectional"))
    )
    (net (code "79") (name "unconnected-(U1-PB0-Pad18)") (class "Default")
      (node (ref "U1") (pin "18") (pinfunction "PB0_18") (pintype "bidirectional"))
    )
    (net (code "80") (name "unconnected-(U1-PB1-Pad19)") (class "Default")
      (node (ref "U1") (pin "19") (pinfunction "PB1_19") (pintype "bidirectional"))
    )
    (net (code "81") (name "unconnected-(U1-PB3{slash}JTDO-Pad39)") (class "Default")
      (node (ref "U1") (pin "39") (pinfunction "PB3/JTDO_39") (pintype "bidirectional"))
    )
    (net (code "82") (name "unconnected-(U1-PB4{slash}JNTRST-Pad40)") (class "Default")
      (node (ref "U1") (pin "40") (pinfunction "PB4/JNTRST_40") (pintype "bidirectional"))
    )
    (net (code "83") (name "unconnected-(U1-PB14-Pad27)") (class "Default")
      (node (ref "U1") (pin "27") (pinfunction "PB14_27") (pintype "bidirectional"))
    )
    (net (code "84") (name "unconnected-(U1-PB15-Pad28)") (class "Default")
      (node (ref "U1") (pin "28") (pinfunction "PB15_28") (pintype "bidirectional"))
    )
    (net (code "85") (name "unconnected-(U1-VBAT-Pad1)") (class "Default")
      (node (ref "U1") (pin "1") (pinfunction "VBAT_1") (pintype "power_in"))
    )
    (net (code "86") (name "unconnected-(U4-ENA-Pad5)") (class "Default")
      (node (ref "U4") (pin "5") (pinfunction "ENA_5") (pintype "passive+no_connect"))
    )
    (net (code "87") (name "unconnected-(U4-NC-Pad2)") (class "Default")
      (node (ref "U4") (pin "2") (pinfunction "NC_2") (pintype "passive"))
    )
    (net (code "88") (name "unconnected-(U4-NC-Pad3)") (class "Default")
      (node (ref "U4") (pin "3") (pinfunction "NC_3") (pintype "passive"))
    )
    (net (code "89") (name "unconnected-(U5-A8-Pad9)") (class "Default")
      (node (ref "U5") (pin "9") (pinfunction "A8_9") (pintype "passive"))
    )
    (net (code "90") (name "unconnected-(U5-B8-Pad12)") (class "Default")
      (node (ref "U5") (pin "12") (pinfunction "B8_12") (pintype "passive"))
    )
  )
)
